# USB_midi_controller.net
KiCad netlist of a schematic drawn in EAGLE
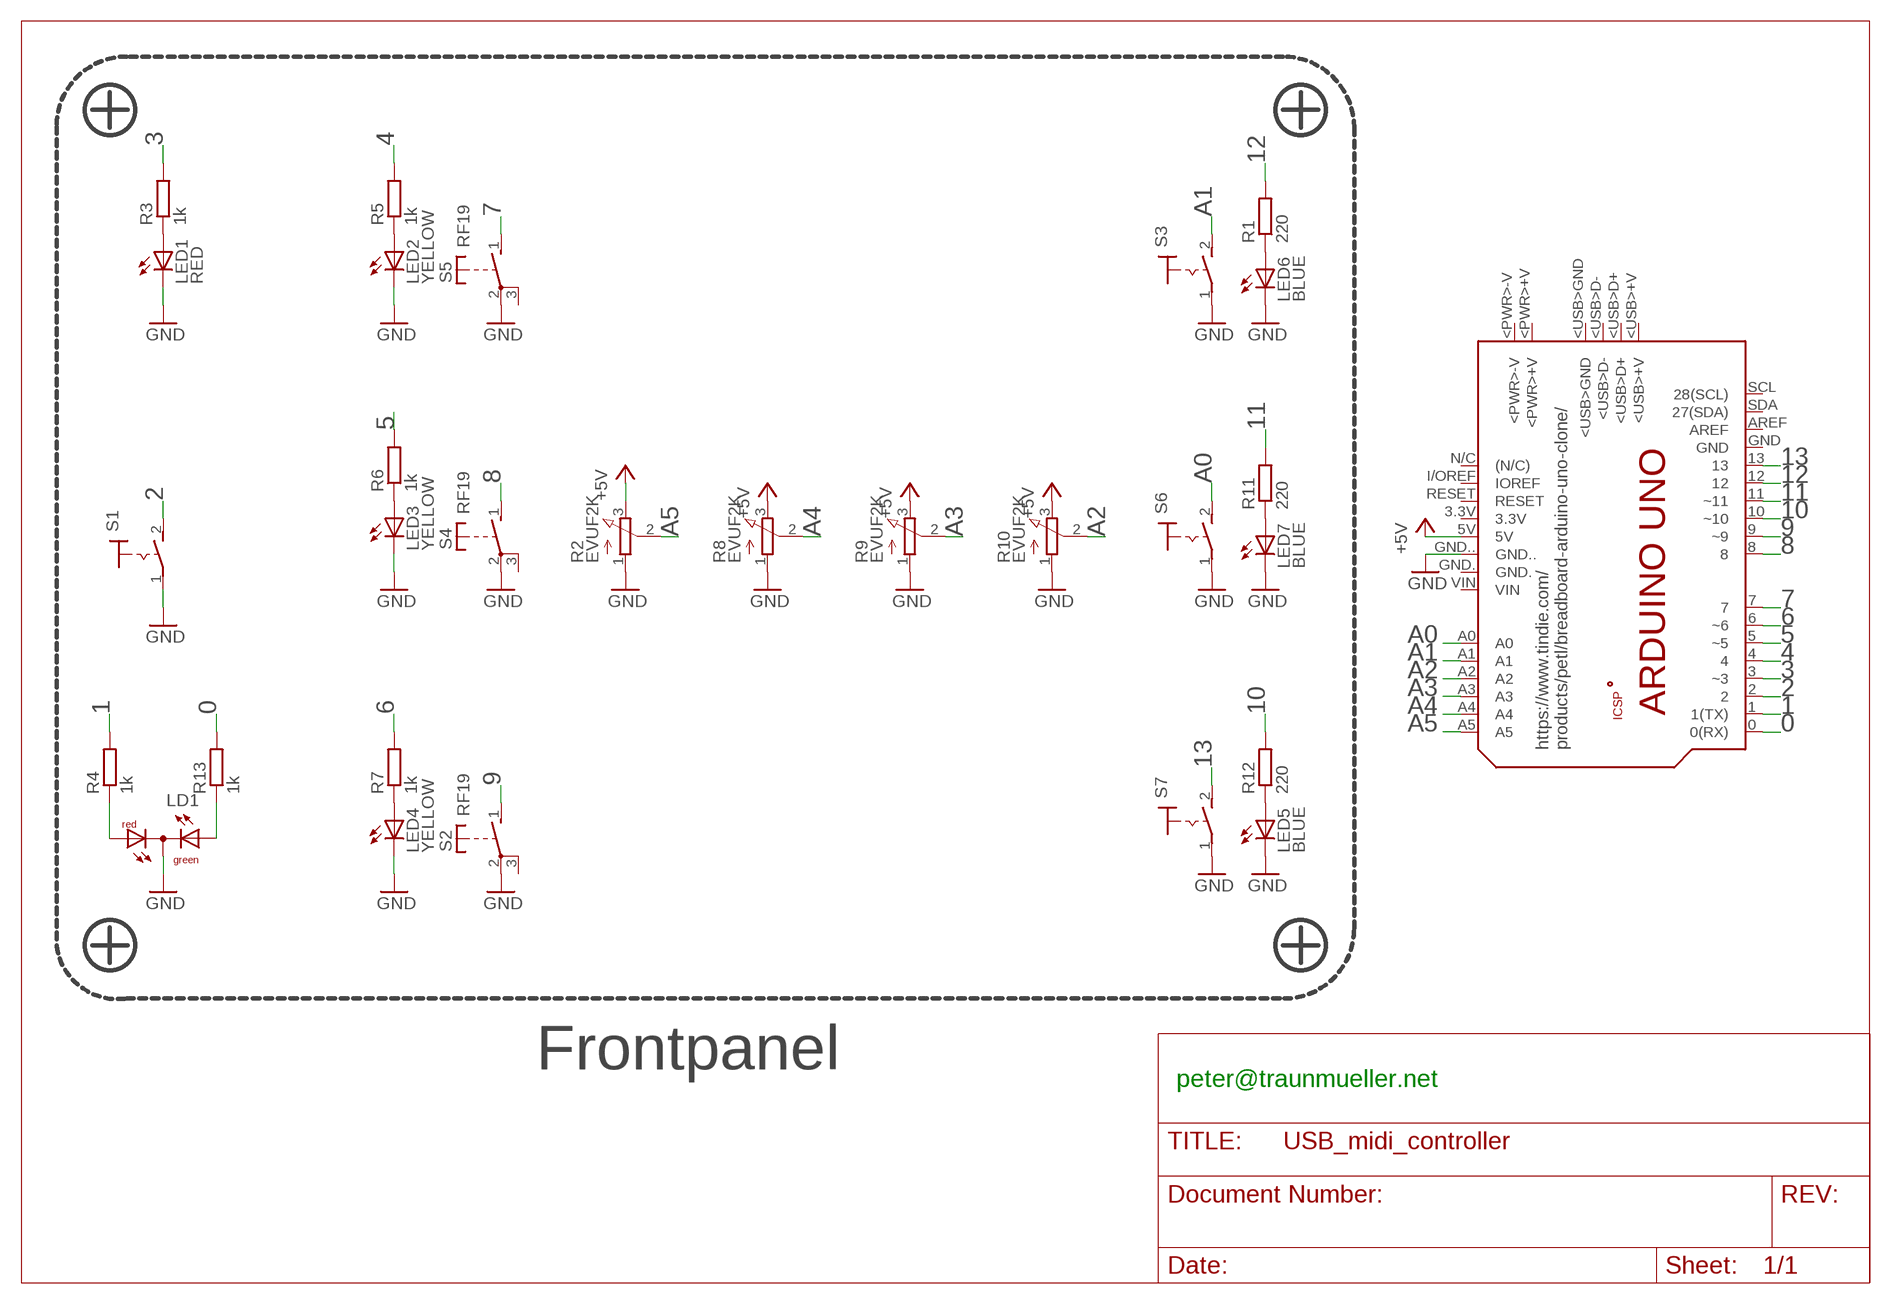
[diagram p0: schematic, sheet 1]

(export (version "E")
  (design (tool "Eeschema 10.0.6"))
  (components
    (comp (ref "LD1")
      (value "DUOLED-RG-C")
      (footprint "eagle-import:DUOLED-C-5MM")
      (libsource (lib "eagle-import") (part "DUOLED-RG-C"))
    )
    (comp (ref "LED1")
      (value "RED")
      (footprint "eagle-import:LED5MM")
      (libsource (lib "eagle-import") (part "LED5MM"))
    )
    (comp (ref "LED2")
      (value "YELLOW")
      (footprint "eagle-import:LED5MM")
      (libsource (lib "eagle-import") (part "LED5MM"))
    )
    (comp (ref "LED3")
      (value "YELLOW")
      (footprint "eagle-import:LED5MM")
      (libsource (lib "eagle-import") (part "LED5MM"))
    )
    (comp (ref "LED4")
      (value "YELLOW")
      (footprint "eagle-import:LED5MM")
      (libsource (lib "eagle-import") (part "LED5MM"))
    )
    (comp (ref "LED5")
      (value "BLUE")
      (footprint "eagle-import:LED5MM")
      (libsource (lib "eagle-import") (part "LED5MM"))
    )
    (comp (ref "LED6")
      (value "BLUE")
      (footprint "eagle-import:LED5MM")
      (libsource (lib "eagle-import") (part "LED5MM"))
    )
    (comp (ref "LED7")
      (value "BLUE")
      (footprint "eagle-import:LED5MM")
      (libsource (lib "eagle-import") (part "LED5MM"))
    )
    (comp (ref "PCB1")
      (value "ARDUINO_UNO")
      (footprint "eagle-import:ARDUINO_UNO")
      (libsource (lib "eagle-import") (part "ARDUINO_UNO"))
    )
    (comp (ref "R1")
      (value "220")
      (footprint "eagle-import:R0805")
      (libsource (lib "eagle-import") (part "R-EU_R0805"))
    )
    (comp (ref "R2")
      (value "EVUF2K")
      (footprint "eagle-import:EVUFXK")
      (libsource (lib "eagle-import") (part "EVUF2K"))
    )
    (comp (ref "R3")
      (value "1k")
      (footprint "eagle-import:R0805")
      (libsource (lib "eagle-import") (part "R-EU_R0805"))
    )
    (comp (ref "R4")
      (value "1k")
      (footprint "eagle-import:R0805")
      (libsource (lib "eagle-import") (part "R-EU_R0805"))
    )
    (comp (ref "R5")
      (value "1k")
      (footprint "eagle-import:R0805")
      (libsource (lib "eagle-import") (part "R-EU_R0805"))
    )
    (comp (ref "R6")
      (value "1k")
      (footprint "eagle-import:R0805")
      (libsource (lib "eagle-import") (part "R-EU_R0805"))
    )
    (comp (ref "R7")
      (value "1k")
      (footprint "eagle-import:R0805")
      (libsource (lib "eagle-import") (part "R-EU_R0805"))
    )
    (comp (ref "R8")
      (value "EVUF2K")
      (footprint "eagle-import:EVUFXK")
      (libsource (lib "eagle-import") (part "EVUF2K"))
    )
    (comp (ref "R9")
      (value "EVUF2K")
      (footprint "eagle-import:EVUFXK")
      (libsource (lib "eagle-import") (part "EVUF2K"))
    )
    (comp (ref "R10")
      (value "EVUF2K")
      (footprint "eagle-import:EVUFXK")
      (libsource (lib "eagle-import") (part "EVUF2K"))
    )
    (comp (ref "R11")
      (value "220")
      (footprint "eagle-import:R0805")
      (libsource (lib "eagle-import") (part "R-EU_R0805"))
    )
    (comp (ref "R12")
      (value "220")
      (footprint "eagle-import:R0805")
      (libsource (lib "eagle-import") (part "R-EU_R0805"))
    )
    (comp (ref "R13")
      (value "1k")
      (footprint "eagle-import:R0805")
      (libsource (lib "eagle-import") (part "R-EU_R0805"))
    )
    (comp (ref "S1")
      (value "KSR224G")
      (footprint "eagle-import:KSR224G")
      (libsource (lib "eagle-import") (part "KSR224G"))
    )
    (comp (ref "S2")
      (value "RF19")
      (footprint "eagle-import:RF19")
      (libsource (lib "eagle-import") (part "RF19"))
    )
    (comp (ref "S3")
      (value "KSR224G")
      (footprint "eagle-import:KSR224G")
      (libsource (lib "eagle-import") (part "KSR224G"))
    )
    (comp (ref "S4")
      (value "RF19")
      (footprint "eagle-import:RF19")
      (libsource (lib "eagle-import") (part "RF19"))
    )
    (comp (ref "S5")
      (value "RF19")
      (footprint "eagle-import:RF19")
      (libsource (lib "eagle-import") (part "RF19"))
    )
    (comp (ref "S6")
      (value "KSR224G")
      (footprint "eagle-import:KSR224G")
      (libsource (lib "eagle-import") (part "KSR224G"))
    )
    (comp (ref "S7")
      (value "KSR224G")
      (footprint "eagle-import:KSR224G")
      (libsource (lib "eagle-import") (part "KSR224G"))
    )
  )
  (nets
    (net (code "1") (name "+5V") (class "Default")
      (node (ref "PCB1") (pin "5V") (pinfunction "5V_5V") (pintype "bidirectional"))
      (node (ref "R10") (pin "3") (pinfunction "E_3") (pintype "passive"))
      (node (ref "R2") (pin "3") (pinfunction "E_3") (pintype "passive"))
      (node (ref "R8") (pin "3") (pinfunction "E_3") (pintype "passive"))
      (node (ref "R9") (pin "3") (pinfunction "E_3") (pintype "passive"))
    )
    (net (code "2") (name "/0") (class "Default")
      (node (ref "PCB1") (pin "0") (pinfunction "0(RX)_0") (pintype "bidirectional"))
      (node (ref "R13") (pin "2") (pinfunction "2_2") (pintype "passive"))
    )
    (net (code "3") (name "/1") (class "Default")
      (node (ref "PCB1") (pin "1") (pinfunction "1(TX)_1") (pintype "bidirectional"))
      (node (ref "R4") (pin "2") (pinfunction "2_2") (pintype "passive"))
    )
    (net (code "4") (name "/2") (class "Default")
      (node (ref "PCB1") (pin "2") (pinfunction "2_2") (pintype "bidirectional"))
      (node (ref "S1") (pin "2") (pinfunction "S_2") (pintype "passive"))
    )
    (net (code "5") (name "/3") (class "Default")
      (node (ref "PCB1") (pin "3") (pinfunction "~{3}_3") (pintype "bidirectional"))
      (node (ref "R3") (pin "2") (pinfunction "2_2") (pintype "passive"))
    )
    (net (code "6") (name "/4") (class "Default")
      (node (ref "PCB1") (pin "4") (pinfunction "4_4") (pintype "bidirectional"))
      (node (ref "R5") (pin "2") (pinfunction "2_2") (pintype "passive"))
    )
    (net (code "7") (name "/5") (class "Default")
      (node (ref "PCB1") (pin "5") (pinfunction "~{5}_5") (pintype "bidirectional"))
      (node (ref "R6") (pin "2") (pinfunction "2_2") (pintype "passive"))
    )
    (net (code "8") (name "/6") (class "Default")
      (node (ref "PCB1") (pin "6") (pinfunction "~{6}_6") (pintype "bidirectional"))
      (node (ref "R7") (pin "2") (pinfunction "2_2") (pintype "passive"))
    )
    (net (code "9") (name "/7") (class "Default")
      (node (ref "PCB1") (pin "7") (pinfunction "7_7") (pintype "bidirectional"))
      (node (ref "S5") (pin "1") (pinfunction "S_1") (pintype "passive"))
    )
    (net (code "10") (name "/8") (class "Default")
      (node (ref "PCB1") (pin "8") (pinfunction "8_8") (pintype "bidirectional"))
      (node (ref "S4") (pin "1") (pinfunction "S_1") (pintype "passive"))
    )
    (net (code "11") (name "/9") (class "Default")
      (node (ref "PCB1") (pin "9") (pinfunction "~{9}_9") (pintype "bidirectional"))
      (node (ref "S2") (pin "1") (pinfunction "S_1") (pintype "passive"))
    )
    (net (code "12") (name "/10") (class "Default")
      (node (ref "PCB1") (pin "10") (pinfunction "~{10}_10") (pintype "bidirectional"))
      (node (ref "R12") (pin "2") (pinfunction "2_2") (pintype "passive"))
    )
    (net (code "13") (name "/11") (class "Default")
      (node (ref "PCB1") (pin "11") (pinfunction "~{11}_11") (pintype "bidirectional"))
      (node (ref "R11") (pin "2") (pinfunction "2_2") (pintype "passive"))
    )
    (net (code "14") (name "/12") (class "Default")
      (node (ref "PCB1") (pin "12") (pinfunction "12_12") (pintype "bidirectional"))
      (node (ref "R1") (pin "2") (pinfunction "2_2") (pintype "passive"))
    )
    (net (code "15") (name "/13") (class "Default")
      (node (ref "PCB1") (pin "13") (pinfunction "13_13") (pintype "bidirectional"))
      (node (ref "S7") (pin "2") (pinfunction "S_2") (pintype "passive"))
    )
    (net (code "16") (name "/A0") (class "Default")
      (node (ref "PCB1") (pin "A0") (pinfunction "A0_A0") (pintype "bidirectional"))
      (node (ref "S6") (pin "2") (pinfunction "S_2") (pintype "passive"))
    )
    (net (code "17") (name "/A1") (class "Default")
      (node (ref "PCB1") (pin "A1") (pinfunction "A1_A1") (pintype "bidirectional"))
      (node (ref "S3") (pin "2") (pinfunction "S_2") (pintype "passive"))
    )
    (net (code "18") (name "/A2") (class "Default")
      (node (ref "PCB1") (pin "A2") (pinfunction "A2_A2") (pintype "bidirectional"))
      (node (ref "R10") (pin "2") (pinfunction "S_2") (pintype "passive"))
    )
    (net (code "19") (name "/A3") (class "Default")
      (node (ref "PCB1") (pin "A3") (pinfunction "A3_A3") (pintype "bidirectional"))
      (node (ref "R9") (pin "2") (pinfunction "S_2") (pintype "passive"))
    )
    (net (code "20") (name "/A4") (class "Default")
      (node (ref "PCB1") (pin "A4") (pinfunction "A4_A4") (pintype "bidirectional"))
      (node (ref "R8") (pin "2") (pinfunction "S_2") (pintype "passive"))
    )
    (net (code "21") (name "/A5") (class "Default")
      (node (ref "PCB1") (pin "A5") (pinfunction "A5_A5") (pintype "bidirectional"))
      (node (ref "R2") (pin "2") (pinfunction "S_2") (pintype "passive"))
    )
    (net (code "22") (name "GND") (class "Default")
      (node (ref "LD1") (pin "C") (pinfunction "C_C") (pintype "passive"))
      (node (ref "LED1") (pin "K") (pinfunction "C_K") (pintype "passive"))
      (node (ref "LED2") (pin "K") (pinfunction "C_K") (pintype "passive"))
      (node (ref "LED3") (pin "K") (pinfunction "C_K") (pintype "passive"))
      (node (ref "LED4") (pin "K") (pinfunction "C_K") (pintype "passive"))
      (node (ref "LED5") (pin "K") (pinfunction "C_K") (pintype "passive"))
      (node (ref "LED6") (pin "K") (pinfunction "C_K") (pintype "passive"))
      (node (ref "LED7") (pin "K") (pinfunction "C_K") (pintype "passive"))
      (node (ref "PCB1") (pin "GND..") (pinfunction "GND.._GND..") (pintype "bidirectional"))
      (node (ref "R10") (pin "1") (pinfunction "A_1") (pintype "passive"))
      (node (ref "R2") (pin "1") (pinfunction "A_1") (pintype "passive"))
      (node (ref "R8") (pin "1") (pinfunction "A_1") (pintype "passive"))
      (node (ref "R9") (pin "1") (pinfunction "A_1") (pintype "passive"))
      (node (ref "S1") (pin "1") (pinfunction "P_1") (pintype "passive"))
      (node (ref "S2") (pin "2") (pinfunction "P_2") (pintype "passive"))
      (node (ref "S3") (pin "1") (pinfunction "P_1") (pintype "passive"))
      (node (ref "S4") (pin "2") (pinfunction "P_2") (pintype "passive"))
      (node (ref "S5") (pin "2") (pinfunction "P_2") (pintype "passive"))
      (node (ref "S6") (pin "1") (pinfunction "P_1") (pintype "passive"))
      (node (ref "S7") (pin "1") (pinfunction "P_1") (pintype "passive"))
    )
    (net (code "23") (name "Net-(LD1-AG)") (class "Default")
      (node (ref "LD1") (pin "AX") (pinfunction "AG_AX") (pintype "passive"))
      (node (ref "R13") (pin "1") (pinfunction "1_1") (pintype "passive"))
    )
    (net (code "24") (name "Net-(LD1-PadAR)") (class "Default")
      (node (ref "LD1") (pin "AR") (pinfunction "AR_AR") (pintype "passive"))
      (node (ref "R4") (pin "1") (pinfunction "1_1") (pintype "passive"))
    )
    (net (code "25") (name "Net-(LED1-PadA)") (class "Default")
      (node (ref "LED1") (pin "A") (pinfunction "A_A") (pintype "passive"))
      (node (ref "R3") (pin "1") (pinfunction "1_1") (pintype "passive"))
    )
    (net (code "26") (name "Net-(LED2-PadA)") (class "Default")
      (node (ref "LED2") (pin "A") (pinfunction "A_A") (pintype "passive"))
      (node (ref "R5") (pin "1") (pinfunction "1_1") (pintype "passive"))
    )
    (net (code "27") (name "Net-(LED3-PadA)") (class "Default")
      (node (ref "LED3") (pin "A") (pinfunction "A_A") (pintype "passive"))
      (node (ref "R6") (pin "1") (pinfunction "1_1") (pintype "passive"))
    )
    (net (code "28") (name "Net-(LED4-PadA)") (class "Default")
      (node (ref "LED4") (pin "A") (pinfunction "A_A") (pintype "passive"))
      (node (ref "R7") (pin "1") (pinfunction "1_1") (pintype "passive"))
    )
    (net (code "29") (name "Net-(LED5-PadA)") (class "Default")
      (node (ref "LED5") (pin "A") (pinfunction "A_A") (pintype "passive"))
      (node (ref "R12") (pin "1") (pinfunction "1_1") (pintype "passive"))
    )
    (net (code "30") (name "Net-(LED6-PadA)") (class "Default")
      (node (ref "LED6") (pin "A") (pinfunction "A_A") (pintype "passive"))
      (node (ref "R1") (pin "1") (pinfunction "1_1") (pintype "passive"))
    )
    (net (code "31") (name "Net-(LED7-PadA)") (class "Default")
      (node (ref "LED7") (pin "A") (pinfunction "A_A") (pintype "passive"))
      (node (ref "R11") (pin "1") (pinfunction "1_1") (pintype "passive"))
    )
    (net (code "32") (name "unconnected-(PCB1-(N{slash}C)-PadN{slash}C)") (class "Default")
      (node (ref "PCB1") (pin "N/C") (pinfunction "(N/C)_N/C") (pintype "bidirectional"))
    )
    (net (code "33") (name "unconnected-(PCB1-27(SDA)-PadSDA)") (class "Default")
      (node (ref "PCB1") (pin "SDA") (pinfunction "27(SDA)_SDA") (pintype "bidirectional"))
    )
    (net (code "34") (name "unconnected-(PCB1-28(SCL)-PadSCL)") (class "Default")
      (node (ref "PCB1") (pin "SCL") (pinfunction "28(SCL)_SCL") (pintype "bidirectional"))
    )
    (net (code "35") (name "unconnected-(PCB1-IOREF-PadI{slash}OREF)") (class "Default")
      (node (ref "PCB1") (pin "I/OREF") (pinfunction "IOREF_I/OREF") (pintype "bidirectional"))
    )
    (net (code "36") (name "unconnected-(PCB1-Pad+5V)") (class "Default")
      (node (ref "PCB1") (pin "+5V") (pinfunction "+5V_+5V") (pintype "bidirectional"))
    )
    (net (code "37") (name "unconnected-(PCB1-Pad3.3V)") (class "Default")
      (node (ref "PCB1") (pin "3.3V") (pinfunction "3.3V_3.3V") (pintype "bidirectional"))
    )
    (net (code "38") (name "unconnected-(PCB1-Pad<PWR>+V)") (class "Default")
      (node (ref "PCB1") (pin "<PWR>+V") (pinfunction "<PWR>+V_<PWR>+V") (pintype "bidirectional"))
    )
    (net (code "39") (name "unconnected-(PCB1-Pad<PWR>-V)") (class "Default")
      (node (ref "PCB1") (pin "<PWR>-V") (pinfunction "<PWR>-V_<PWR>-V") (pintype "bidirectional"))
    )
    (net (code "40") (name "unconnected-(PCB1-Pad<USB>+V)") (class "Default")
      (node (ref "PCB1") (pin "<USB>+V") (pinfunction "<USB>+V_<USB>+V") (pintype "bidirectional"))
    )
    (net (code "41") (name "unconnected-(PCB1-Pad<USB>D+)") (class "Default")
      (node (ref "PCB1") (pin "<USB>D+") (pinfunction "<USB>D+_<USB>D+") (pintype "bidirectional"))
    )
    (net (code "42") (name "unconnected-(PCB1-Pad<USB>D-)") (class "Default")
      (node (ref "PCB1") (pin "<USB>D-") (pinfunction "<USB>D-_<USB>D-") (pintype "bidirectional"))
    )
    (net (code "43") (name "unconnected-(PCB1-Pad<USB>GND)") (class "Default")
      (node (ref "PCB1") (pin "<USB>GND") (pinfunction "<USB>GND_<USB>GND") (pintype "bidirectional"))
    )
    (net (code "44") (name "unconnected-(PCB1-PadAREF)") (class "Default")
      (node (ref "PCB1") (pin "AREF") (pinfunction "AREF_AREF") (pintype "bidirectional"))
    )
    (net (code "45") (name "unconnected-(PCB1-PadGND)") (class "Default")
      (node (ref "PCB1") (pin "GND") (pinfunction "GND_GND") (pintype "bidirectional"))
    )
    (net (code "46") (name "unconnected-(PCB1-PadGND.)") (class "Default")
      (node (ref "PCB1") (pin "GND.") (pinfunction "GND._GND.") (pintype "bidirectional"))
    )
    (net (code "47") (name "unconnected-(PCB1-PadGND_)") (class "Default")
      (node (ref "PCB1") (pin "GND_") (pinfunction "GND__GND_") (pintype "bidirectional"))
    )
    (net (code "48") (name "unconnected-(PCB1-PadMISO)") (class "Default")
      (node (ref "PCB1") (pin "MISO") (pinfunction "MISO_MISO") (pintype "bidirectional"))
    )
    (net (code "49") (name "unconnected-(PCB1-PadMOSI)") (class "Default")
      (node (ref "PCB1") (pin "MOSI") (pinfunction "MOSI_MOSI") (pintype "bidirectional"))
    )
    (net (code "50") (name "unconnected-(PCB1-PadRESET)") (class "Default")
      (node (ref "PCB1") (pin "RESET") (pinfunction "RESET_RESET") (pintype "bidirectional"))
    )
    (net (code "51") (name "unconnected-(PCB1-PadRESET.)") (class "Default")
      (node (ref "PCB1") (pin "RESET.") (pinfunction "RESET._RESET.") (pintype "bidirectional"))
    )
    (net (code "52") (name "unconnected-(PCB1-PadSCK)") (class "Default")
      (node (ref "PCB1") (pin "SCK") (pinfunction "SCK_SCK") (pintype "bidirectional"))
    )
    (net (code "53") (name "unconnected-(PCB1-PadVIN)") (class "Default")
      (node (ref "PCB1") (pin "VIN") (pinfunction "VIN_VIN") (pintype "bidirectional"))
    )
    (net (code "54") (name "unconnected-(S2-P-Pad3)") (class "Default")
      (node (ref "S2") (pin "3") (pinfunction "P_3") (pintype "passive"))
    )
    (net (code "55") (name "unconnected-(S4-P-Pad3)") (class "Default")
      (node (ref "S4") (pin "3") (pinfunction "P_3") (pintype "passive"))
    )
    (net (code "56") (name "unconnected-(S5-P-Pad3)") (class "Default")
      (node (ref "S5") (pin "3") (pinfunction "P_3") (pintype "passive"))
    )
  )
)
